# llc.net
KiCad netlist of a schematic drawn in EasyEDA Pro
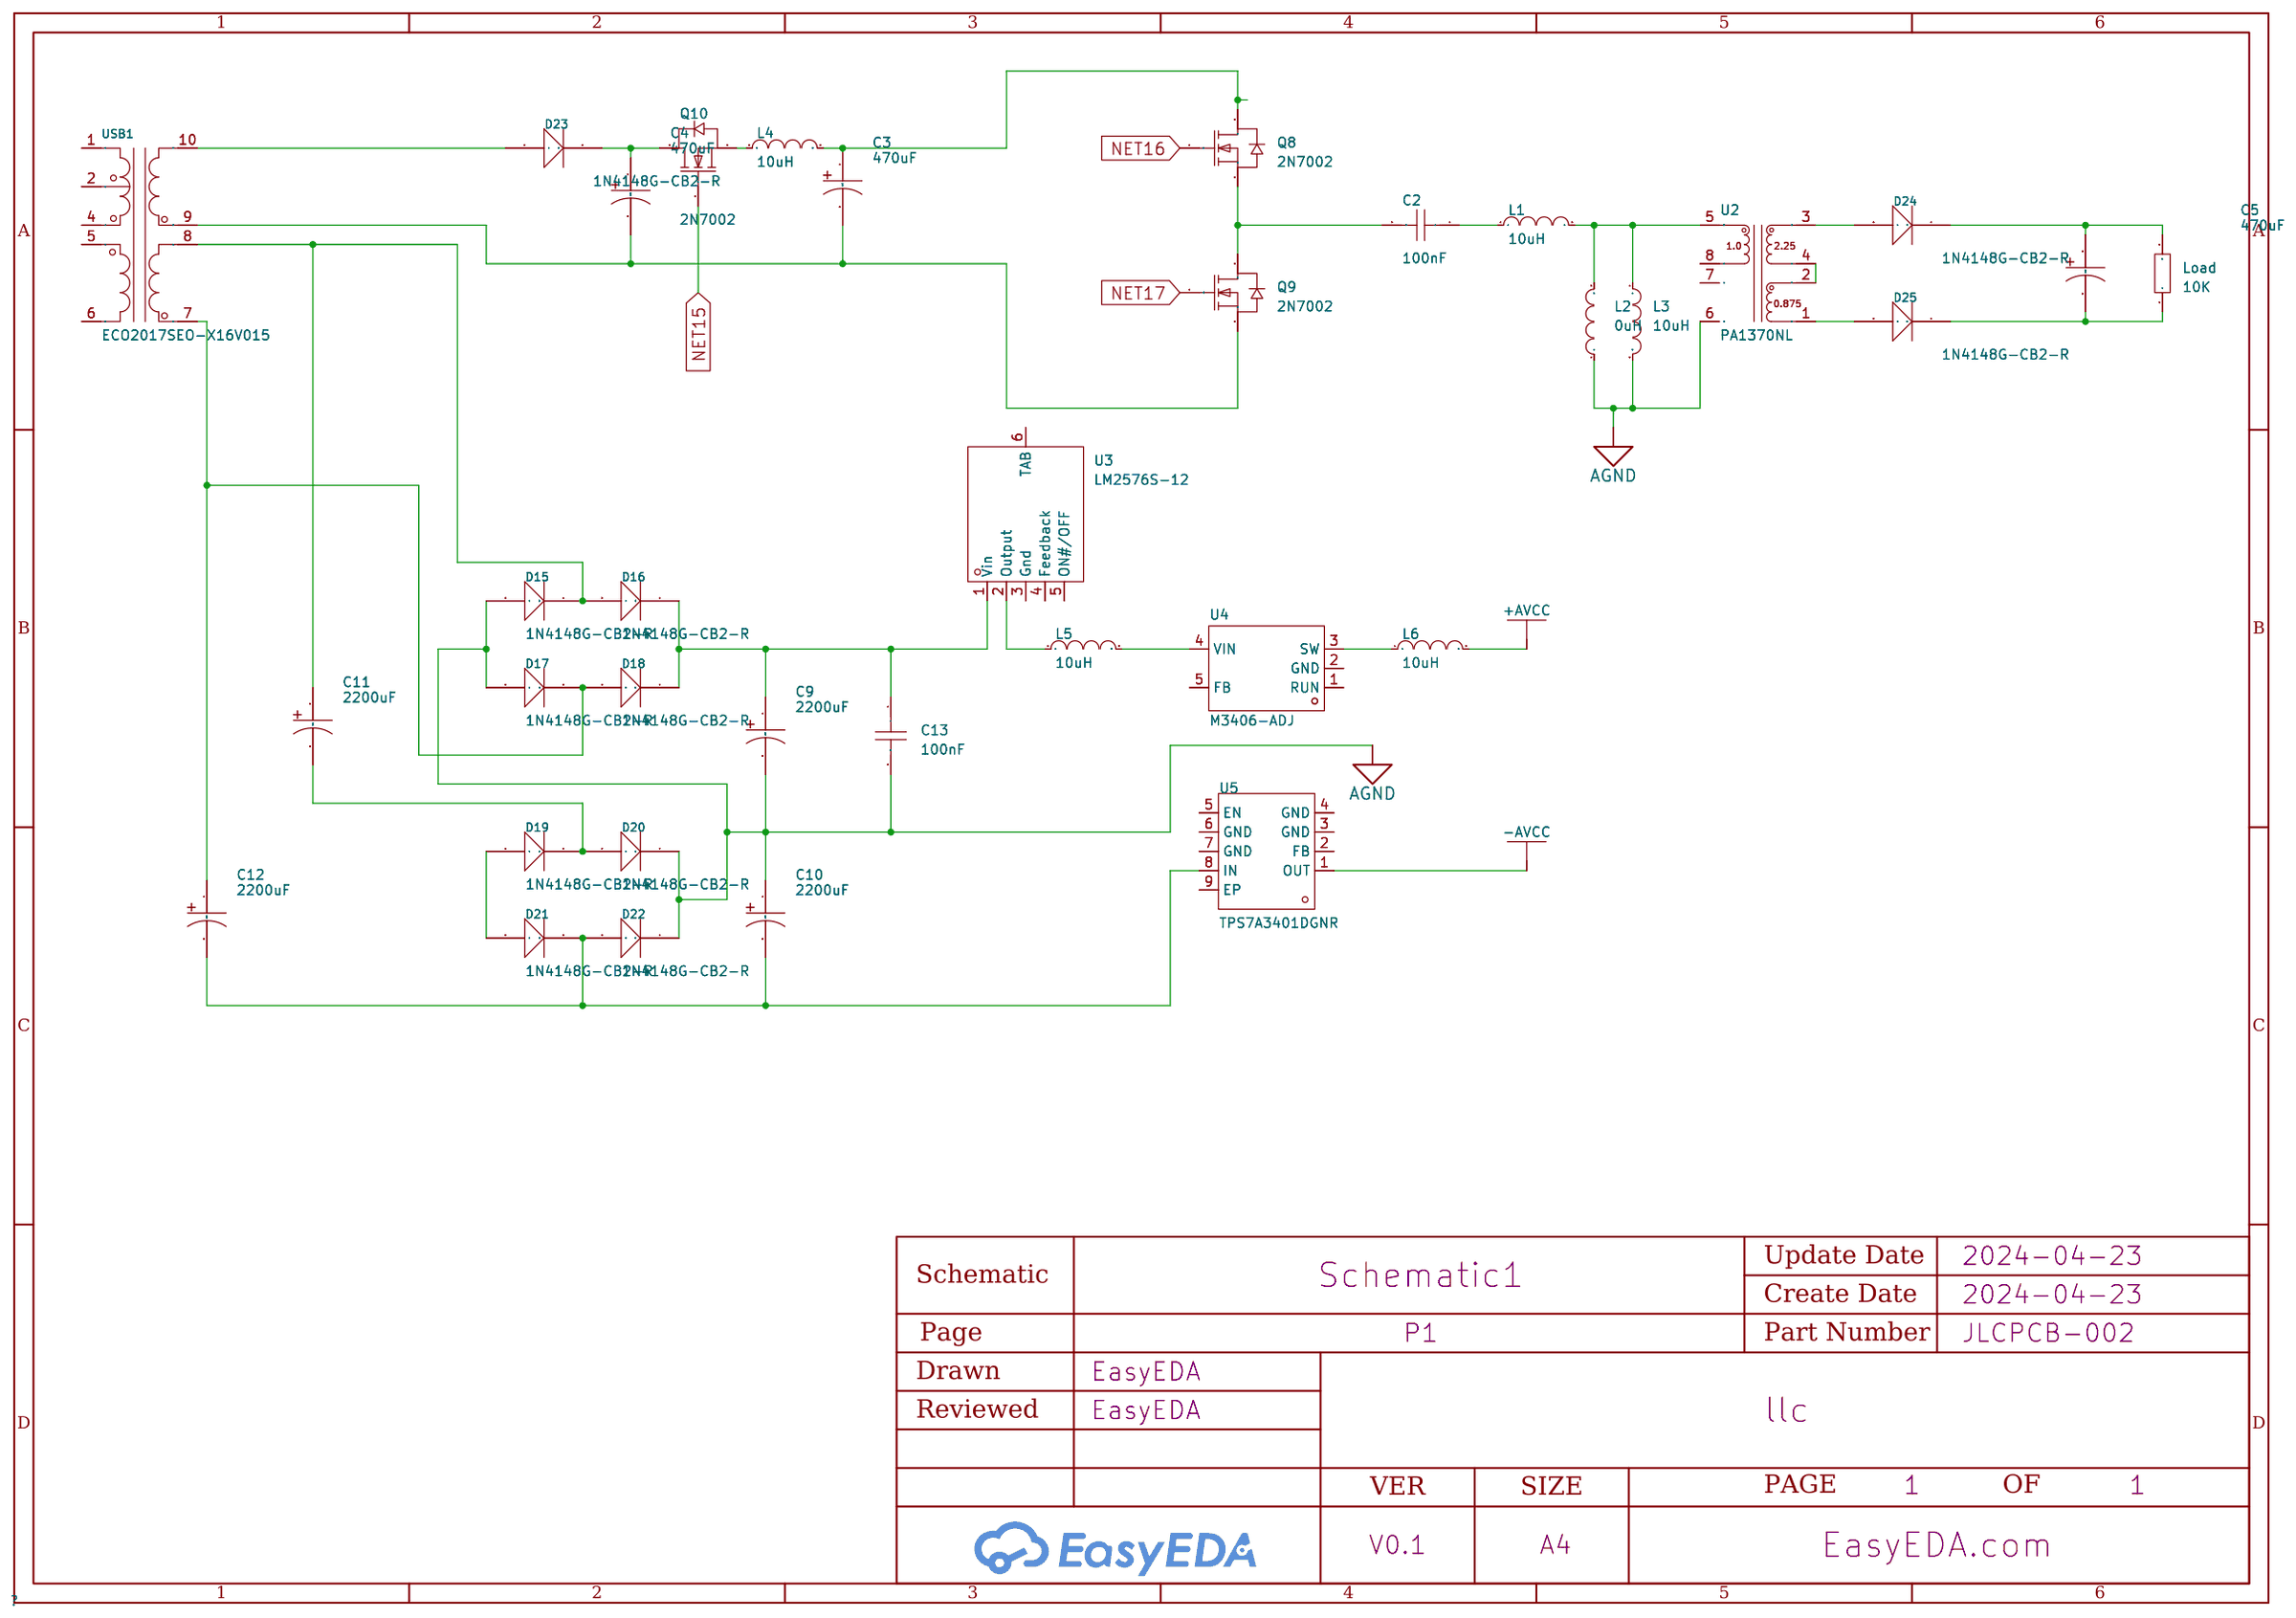
[diagram p0: P1]
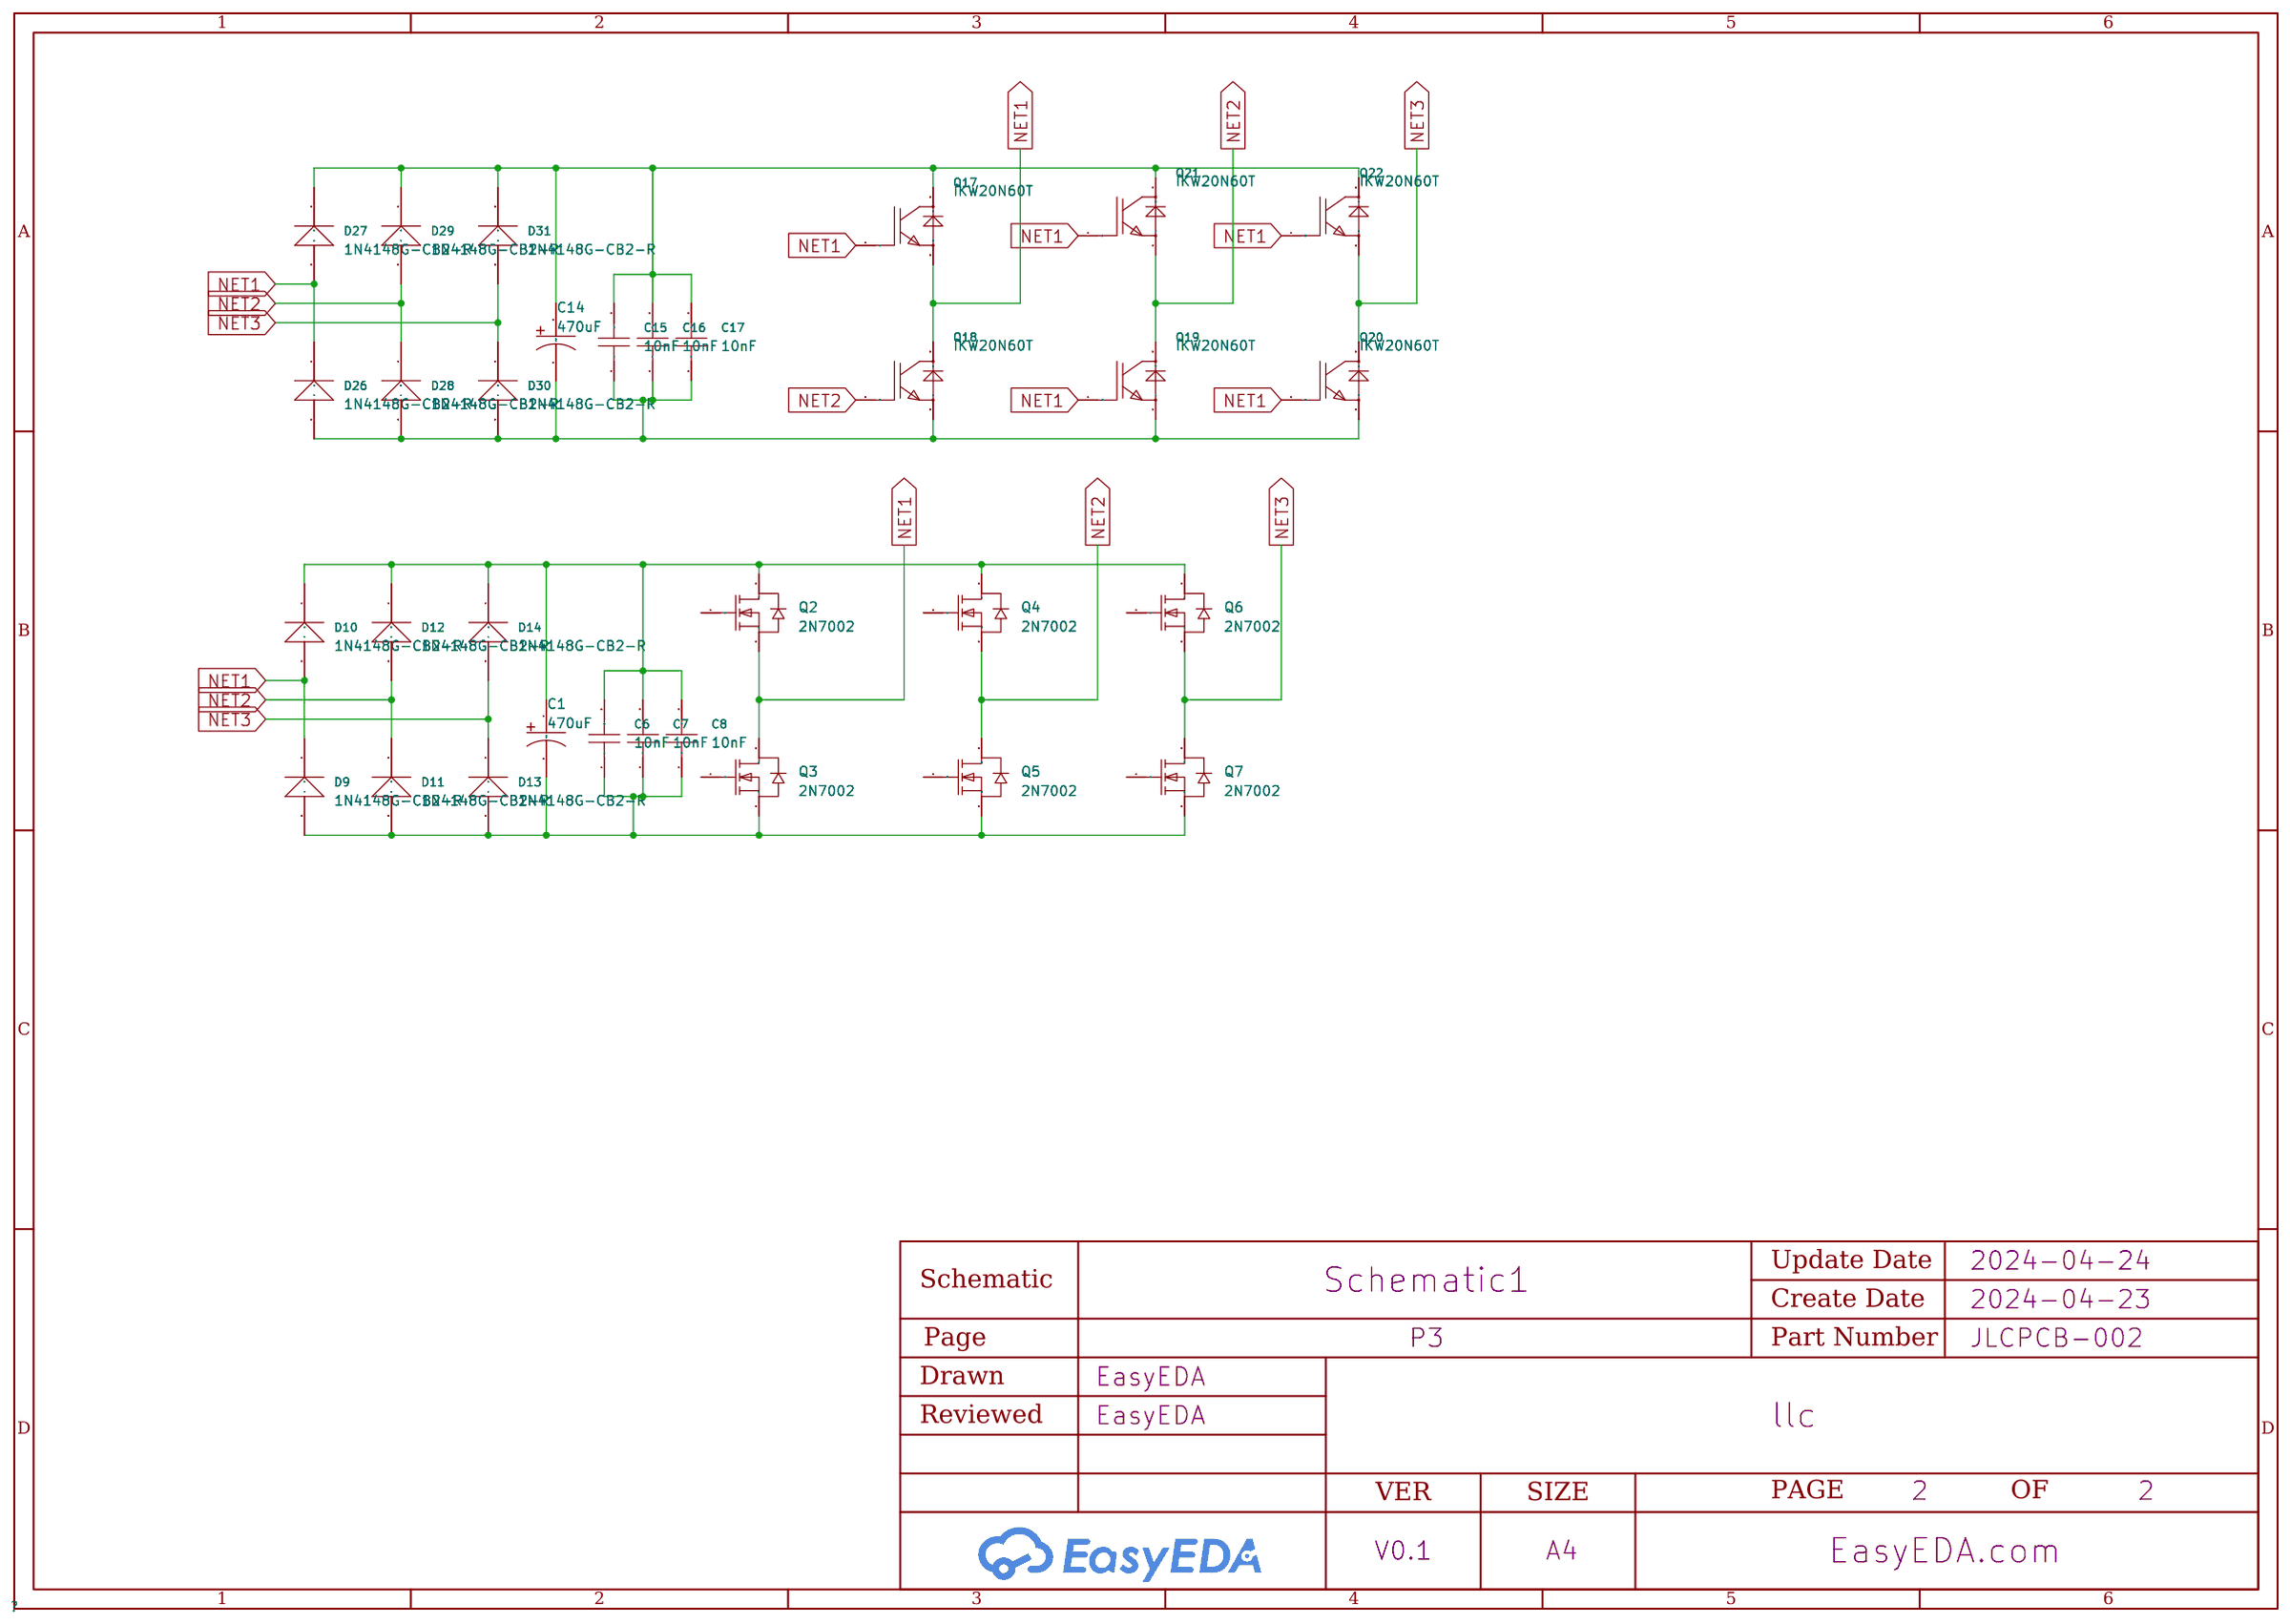
[diagram p1: P3]

(export (version "E")
  (design (tool "Eeschema 10.0.6"))
  (components
    (comp (ref "C2")
      (value "100nF")
      (footprint "easyedapro:C0603")
      (libsource (lib "easyedapro") (part "CAP"))
    )
    (comp (ref "C3")
      (value "470uF")
      (footprint "easyedapro:CAP-TH_BD35.0-P10.00-D2.3-FD")
      (fields (field (name "Manufacturer Part") "B43545S7477M001") (field (name "Manufacturer") "TDK"))
      (libsource (lib "easyedapro") (part "B43545S7477M001"))
    )
    (comp (ref "C4")
      (value "470uF")
      (footprint "easyedapro:CAP-TH_BD35.0-P10.00-D2.3-FD")
      (fields (field (name "Manufacturer Part") "B43545S7477M001") (field (name "Manufacturer") "TDK"))
      (libsource (lib "easyedapro") (part "B43545S7477M001"))
    )
    (comp (ref "C5")
      (value "470uF")
      (footprint "easyedapro:CAP-TH_BD35.0-P10.00-D2.3-FD")
      (fields (field (name "Manufacturer Part") "B43545S7477M001") (field (name "Manufacturer") "TDK"))
      (libsource (lib "easyedapro") (part "B43545S7477M001"))
    )
    (comp (ref "C9")
      (value "2200uF")
      (footprint "easyedapro:CAP-TH_BD12.5-P5.00-D0.6-FD")
      (fields (field (name "Manufacturer Part") "RGA222M1EBK-1325") (field (name "Manufacturer") "lelon(立隆)"))
      (libsource (lib "easyedapro") (part "RGA222M1EBK-1325"))
    )
    (comp (ref "C10")
      (value "2200uF")
      (footprint "easyedapro:CAP-TH_BD12.5-P5.00-D0.6-FD")
      (fields (field (name "Manufacturer Part") "RGA222M1EBK-1325") (field (name "Manufacturer") "lelon(立隆)"))
      (libsource (lib "easyedapro") (part "RGA222M1EBK-1325"))
    )
    (comp (ref "C11")
      (value "2200uF")
      (footprint "easyedapro:CAP-TH_BD12.5-P5.00-D0.6-FD")
      (fields (field (name "Manufacturer Part") "RGA222M1EBK-1325") (field (name "Manufacturer") "lelon(立隆)"))
      (libsource (lib "easyedapro") (part "RGA222M1EBK-1325"))
    )
    (comp (ref "C12")
      (value "2200uF")
      (footprint "easyedapro:CAP-TH_BD12.5-P5.00-D0.6-FD")
      (fields (field (name "Manufacturer Part") "RGA222M1EBK-1325") (field (name "Manufacturer") "lelon(立隆)"))
      (libsource (lib "easyedapro") (part "RGA222M1EBK-1325"))
    )
    (comp (ref "C13")
      (value "100nF")
      (footprint "easyedapro:C0603")
      (libsource (lib "easyedapro") (part "CAP"))
    )
    (comp (ref "D15")
      (value "1N4148G-CB2-R")
      (footprint "easyedapro:SOD-323_L1.8-W1.3-LS2.5-RD")
      (fields (field (name "Manufacturer") "UTC(友顺)"))
      (libsource (lib "easyedapro") (part "1N4148G-CB2-R"))
    )
    (comp (ref "D16")
      (value "1N4148G-CB2-R")
      (footprint "easyedapro:SOD-323_L1.8-W1.3-LS2.5-RD")
      (fields (field (name "Manufacturer") "UTC(友顺)"))
      (libsource (lib "easyedapro") (part "1N4148G-CB2-R"))
    )
    (comp (ref "D17")
      (value "1N4148G-CB2-R")
      (footprint "easyedapro:SOD-323_L1.8-W1.3-LS2.5-RD")
      (fields (field (name "Manufacturer") "UTC(友顺)"))
      (libsource (lib "easyedapro") (part "1N4148G-CB2-R"))
    )
    (comp (ref "D18")
      (value "1N4148G-CB2-R")
      (footprint "easyedapro:SOD-323_L1.8-W1.3-LS2.5-RD")
      (fields (field (name "Manufacturer") "UTC(友顺)"))
      (libsource (lib "easyedapro") (part "1N4148G-CB2-R"))
    )
    (comp (ref "D19")
      (value "1N4148G-CB2-R")
      (footprint "easyedapro:SOD-323_L1.8-W1.3-LS2.5-RD")
      (fields (field (name "Manufacturer") "UTC(友顺)"))
      (libsource (lib "easyedapro") (part "1N4148G-CB2-R"))
    )
    (comp (ref "D20")
      (value "1N4148G-CB2-R")
      (footprint "easyedapro:SOD-323_L1.8-W1.3-LS2.5-RD")
      (fields (field (name "Manufacturer") "UTC(友顺)"))
      (libsource (lib "easyedapro") (part "1N4148G-CB2-R"))
    )
    (comp (ref "D21")
      (value "1N4148G-CB2-R")
      (footprint "easyedapro:SOD-323_L1.8-W1.3-LS2.5-RD")
      (fields (field (name "Manufacturer") "UTC(友顺)"))
      (libsource (lib "easyedapro") (part "1N4148G-CB2-R"))
    )
    (comp (ref "D22")
      (value "1N4148G-CB2-R")
      (footprint "easyedapro:SOD-323_L1.8-W1.3-LS2.5-RD")
      (fields (field (name "Manufacturer") "UTC(友顺)"))
      (libsource (lib "easyedapro") (part "1N4148G-CB2-R"))
    )
    (comp (ref "D23")
      (value "1N4148G-CB2-R")
      (footprint "easyedapro:SOD-323_L1.8-W1.3-LS2.5-RD")
      (fields (field (name "Manufacturer") "UTC(友顺)"))
      (libsource (lib "easyedapro") (part "1N4148G-CB2-R"))
    )
    (comp (ref "D24")
      (value "1N4148G-CB2-R")
      (footprint "easyedapro:SOD-323_L1.8-W1.3-LS2.5-RD")
      (fields (field (name "Manufacturer") "UTC(友顺)"))
      (libsource (lib "easyedapro") (part "1N4148G-CB2-R"))
    )
    (comp (ref "D25")
      (value "1N4148G-CB2-R")
      (footprint "easyedapro:SOD-323_L1.8-W1.3-LS2.5-RD")
      (fields (field (name "Manufacturer") "UTC(友顺)"))
      (libsource (lib "easyedapro") (part "1N4148G-CB2-R"))
    )
    (comp (ref "L1") (value "10uH") (footprint "easyedapro:L0603") (libsource (lib "easyedapro") (part "电感")))
    (comp (ref "L2") (value "0uH") (footprint "easyedapro:L0603") (libsource (lib "easyedapro") (part "电感")))
    (comp (ref "L3") (value "10uH") (footprint "easyedapro:L0603") (libsource (lib "easyedapro") (part "电感")))
    (comp (ref "L4") (value "10uH") (footprint "easyedapro:L0603") (libsource (lib "easyedapro") (part "电感")))
    (comp (ref "L5") (value "10uH") (footprint "easyedapro:L0603") (libsource (lib "easyedapro") (part "电感")))
    (comp (ref "L6") (value "10uH") (footprint "easyedapro:L0603") (libsource (lib "easyedapro") (part "电感")))
    (comp (ref "Load")
      (value "10K")
      (footprint "easyedapro:R0603")
      (libsource (lib "easyedapro") (part "Res"))
    )
    (comp (ref "Q8")
      (value "2N7002")
      (footprint "easyedapro:SOT-23-3_L2.9-W1.3-P1.90-LS2.4-BR")
      (fields (field (name "Manufacturer") "CJ(江苏长电/长晶)"))
      (libsource (lib "easyedapro") (part "2N7002"))
    )
    (comp (ref "Q9")
      (value "2N7002")
      (footprint "easyedapro:SOT-23-3_L2.9-W1.3-P1.90-LS2.4-BR")
      (fields (field (name "Manufacturer") "CJ(江苏长电/长晶)"))
      (libsource (lib "easyedapro") (part "2N7002"))
    )
    (comp (ref "Q10")
      (value "2N7002")
      (footprint "easyedapro:SOT-23-3_L2.9-W1.3-P1.90-LS2.4-BR")
      (fields (field (name "Manufacturer") "CJ(江苏长电/长晶)"))
      (libsource (lib "easyedapro") (part "2N7002"))
    )
    (comp (ref "U2")
      (value "PA1370NL")
      (footprint "easyedapro:XFMR-SMD_PA1370NL")
      (description "Inductor:20.4uH operating temperature:-40°C~+130°C operating temperature:-40°C~+130°C")
      (fields (field (name "Manufacturer") "PULSE(普思)"))
      (libsource (lib "easyedapro") (part "PA1370NL"))
    )
    (comp (ref "U3")
      (value "LM2576S-12")
      (footprint "easyedapro:TO-263-5_L10.2-W8.9-P1.70-BR")
      (fields (field (name "Manufacturer") "UMW(友台半导体)"))
      (libsource (lib "easyedapro") (part "LM2576S-12_C347414"))
    )
    (comp (ref "U4")
      (value "M3406-ADJ")
      (footprint "easyedapro:SOT-23-5_L3.0-W1.7-P0.95-LS2.8-BR")
      (fields (field (name "Manufacturer") "西安航天民芯"))
      (libsource (lib "easyedapro") (part "M3406"))
    )
    (comp (ref "U5")
      (value "TPS7A3401DGNR")
      (footprint "easyedapro:MSOP-8_L3.0-W3.0-P0.65-LS4.9-BL-EP")
      (fields (field (name "Manufacturer") "TI(德州仪器)"))
      (libsource (lib "easyedapro") (part "TPS7A3401DGNR"))
    )
    (comp (ref "USB1")
      (value "ECO2017SEO-X16V015")
      (footprint "easyedapro:XFMR-TH_ECO2017SEO-X16V015")
      (fields (field (name "Manufacturer") "TDK"))
      (libsource (lib "easyedapro") (part "ECO2017SEO-X16V015"))
    )
    (comp (ref "C1")
      (value "470uF")
      (footprint "easyedapro:CAP-TH_BD35.0-P10.00-D2.3-FD")
      (fields (field (name "Manufacturer Part") "B43545S7477M001") (field (name "Manufacturer") "TDK"))
      (libsource (lib "easyedapro") (part "B43545S7477M001"))
    )
    (comp (ref "C6")
      (value "10nF")
      (footprint "easyedapro:CAP-TH_L14.0-W5.0-P7.50-D0.6-LS3.0")
      (fields
        (field (name "Manufacturer Part") "Y5V103M2KV16CC0204")
        (field (name "Manufacturer") "KNSCHA(科尼盛)")
      )
      (libsource (lib "easyedapro") (part "Y5V103M2KV16CC0204"))
    )
    (comp (ref "C7")
      (value "10nF")
      (footprint "easyedapro:CAP-TH_L14.0-W5.0-P7.50-D0.6-LS3.0")
      (fields
        (field (name "Manufacturer Part") "Y5V103M2KV16CC0204")
        (field (name "Manufacturer") "KNSCHA(科尼盛)")
      )
      (libsource (lib "easyedapro") (part "Y5V103M2KV16CC0204"))
    )
    (comp (ref "C8")
      (value "10nF")
      (footprint "easyedapro:CAP-TH_L14.0-W5.0-P7.50-D0.6-LS3.0")
      (fields
        (field (name "Manufacturer Part") "Y5V103M2KV16CC0204")
        (field (name "Manufacturer") "KNSCHA(科尼盛)")
      )
      (libsource (lib "easyedapro") (part "Y5V103M2KV16CC0204"))
    )
    (comp (ref "C14")
      (value "470uF")
      (footprint "easyedapro:CAP-TH_BD35.0-P10.00-D2.3-FD")
      (fields (field (name "Manufacturer Part") "B43545S7477M001") (field (name "Manufacturer") "TDK"))
      (libsource (lib "easyedapro") (part "B43545S7477M001"))
    )
    (comp (ref "C15")
      (value "10nF")
      (footprint "easyedapro:CAP-TH_L14.0-W5.0-P7.50-D0.6-LS3.0")
      (fields
        (field (name "Manufacturer Part") "Y5V103M2KV16CC0204")
        (field (name "Manufacturer") "KNSCHA(科尼盛)")
      )
      (libsource (lib "easyedapro") (part "Y5V103M2KV16CC0204"))
    )
    (comp (ref "C16")
      (value "10nF")
      (footprint "easyedapro:CAP-TH_L14.0-W5.0-P7.50-D0.6-LS3.0")
      (fields
        (field (name "Manufacturer Part") "Y5V103M2KV16CC0204")
        (field (name "Manufacturer") "KNSCHA(科尼盛)")
      )
      (libsource (lib "easyedapro") (part "Y5V103M2KV16CC0204"))
    )
    (comp (ref "C17")
      (value "10nF")
      (footprint "easyedapro:CAP-TH_L14.0-W5.0-P7.50-D0.6-LS3.0")
      (fields
        (field (name "Manufacturer Part") "Y5V103M2KV16CC0204")
        (field (name "Manufacturer") "KNSCHA(科尼盛)")
      )
      (libsource (lib "easyedapro") (part "Y5V103M2KV16CC0204"))
    )
    (comp (ref "D9")
      (value "1N4148G-CB2-R")
      (footprint "easyedapro:SOD-323_L1.8-W1.3-LS2.5-RD")
      (fields (field (name "Manufacturer") "UTC(友顺)"))
      (libsource (lib "easyedapro") (part "1N4148G-CB2-R"))
    )
    (comp (ref "D10")
      (value "1N4148G-CB2-R")
      (footprint "easyedapro:SOD-323_L1.8-W1.3-LS2.5-RD")
      (fields (field (name "Manufacturer") "UTC(友顺)"))
      (libsource (lib "easyedapro") (part "1N4148G-CB2-R"))
    )
    (comp (ref "D11")
      (value "1N4148G-CB2-R")
      (footprint "easyedapro:SOD-323_L1.8-W1.3-LS2.5-RD")
      (fields (field (name "Manufacturer") "UTC(友顺)"))
      (libsource (lib "easyedapro") (part "1N4148G-CB2-R"))
    )
    (comp (ref "D12")
      (value "1N4148G-CB2-R")
      (footprint "easyedapro:SOD-323_L1.8-W1.3-LS2.5-RD")
      (fields (field (name "Manufacturer") "UTC(友顺)"))
      (libsource (lib "easyedapro") (part "1N4148G-CB2-R"))
    )
    (comp (ref "D13")
      (value "1N4148G-CB2-R")
      (footprint "easyedapro:SOD-323_L1.8-W1.3-LS2.5-RD")
      (fields (field (name "Manufacturer") "UTC(友顺)"))
      (libsource (lib "easyedapro") (part "1N4148G-CB2-R"))
    )
    (comp (ref "D14")
      (value "1N4148G-CB2-R")
      (footprint "easyedapro:SOD-323_L1.8-W1.3-LS2.5-RD")
      (fields (field (name "Manufacturer") "UTC(友顺)"))
      (libsource (lib "easyedapro") (part "1N4148G-CB2-R"))
    )
    (comp (ref "D26")
      (value "1N4148G-CB2-R")
      (footprint "easyedapro:SOD-323_L1.8-W1.3-LS2.5-RD")
      (fields (field (name "Manufacturer") "UTC(友顺)"))
      (libsource (lib "easyedapro") (part "1N4148G-CB2-R"))
    )
    (comp (ref "D27")
      (value "1N4148G-CB2-R")
      (footprint "easyedapro:SOD-323_L1.8-W1.3-LS2.5-RD")
      (fields (field (name "Manufacturer") "UTC(友顺)"))
      (libsource (lib "easyedapro") (part "1N4148G-CB2-R"))
    )
    (comp (ref "D28")
      (value "1N4148G-CB2-R")
      (footprint "easyedapro:SOD-323_L1.8-W1.3-LS2.5-RD")
      (fields (field (name "Manufacturer") "UTC(友顺)"))
      (libsource (lib "easyedapro") (part "1N4148G-CB2-R"))
    )
    (comp (ref "D29")
      (value "1N4148G-CB2-R")
      (footprint "easyedapro:SOD-323_L1.8-W1.3-LS2.5-RD")
      (fields (field (name "Manufacturer") "UTC(友顺)"))
      (libsource (lib "easyedapro") (part "1N4148G-CB2-R"))
    )
    (comp (ref "D30")
      (value "1N4148G-CB2-R")
      (footprint "easyedapro:SOD-323_L1.8-W1.3-LS2.5-RD")
      (fields (field (name "Manufacturer") "UTC(友顺)"))
      (libsource (lib "easyedapro") (part "1N4148G-CB2-R"))
    )
    (comp (ref "D31")
      (value "1N4148G-CB2-R")
      (footprint "easyedapro:SOD-323_L1.8-W1.3-LS2.5-RD")
      (fields (field (name "Manufacturer") "UTC(友顺)"))
      (libsource (lib "easyedapro") (part "1N4148G-CB2-R"))
    )
    (comp (ref "Q2")
      (value "2N7002")
      (footprint "easyedapro:SOT-23-3_L2.9-W1.3-P1.90-LS2.4-BR")
      (fields (field (name "Manufacturer") "CJ(江苏长电/长晶)"))
      (libsource (lib "easyedapro") (part "2N7002"))
    )
    (comp (ref "Q3")
      (value "2N7002")
      (footprint "easyedapro:SOT-23-3_L2.9-W1.3-P1.90-LS2.4-BR")
      (fields (field (name "Manufacturer") "CJ(江苏长电/长晶)"))
      (libsource (lib "easyedapro") (part "2N7002"))
    )
    (comp (ref "Q4")
      (value "2N7002")
      (footprint "easyedapro:SOT-23-3_L2.9-W1.3-P1.90-LS2.4-BR")
      (fields (field (name "Manufacturer") "CJ(江苏长电/长晶)"))
      (libsource (lib "easyedapro") (part "2N7002"))
    )
    (comp (ref "Q5")
      (value "2N7002")
      (footprint "easyedapro:SOT-23-3_L2.9-W1.3-P1.90-LS2.4-BR")
      (fields (field (name "Manufacturer") "CJ(江苏长电/长晶)"))
      (libsource (lib "easyedapro") (part "2N7002"))
    )
    (comp (ref "Q6")
      (value "2N7002")
      (footprint "easyedapro:SOT-23-3_L2.9-W1.3-P1.90-LS2.4-BR")
      (fields (field (name "Manufacturer") "CJ(江苏长电/长晶)"))
      (libsource (lib "easyedapro") (part "2N7002"))
    )
    (comp (ref "Q7")
      (value "2N7002")
      (footprint "easyedapro:SOT-23-3_L2.9-W1.3-P1.90-LS2.4-BR")
      (fields (field (name "Manufacturer") "CJ(江苏长电/长晶)"))
      (libsource (lib "easyedapro") (part "2N7002"))
    )
    (comp (ref "Q17")
      (value "IKW20N60T")
      (footprint "easyedapro:TO-247AC-3_L15.8-W5.0-P5.46-L")
      (fields (field (name "Manufacturer") "Infineon(英飞凌)"))
      (libsource (lib "easyedapro") (part "IKW20N60T"))
    )
    (comp (ref "Q18")
      (value "IKW20N60T")
      (footprint "easyedapro:TO-247AC-3_L15.8-W5.0-P5.46-L")
      (fields (field (name "Manufacturer") "Infineon(英飞凌)"))
      (libsource (lib "easyedapro") (part "IKW20N60T"))
    )
    (comp (ref "Q19")
      (value "IKW20N60T")
      (footprint "easyedapro:TO-247AC-3_L15.8-W5.0-P5.46-L")
      (fields (field (name "Manufacturer") "Infineon(英飞凌)"))
      (libsource (lib "easyedapro") (part "IKW20N60T"))
    )
    (comp (ref "Q20")
      (value "IKW20N60T")
      (footprint "easyedapro:TO-247AC-3_L15.8-W5.0-P5.46-L")
      (fields (field (name "Manufacturer") "Infineon(英飞凌)"))
      (libsource (lib "easyedapro") (part "IKW20N60T"))
    )
    (comp (ref "Q21")
      (value "IKW20N60T")
      (footprint "easyedapro:TO-247AC-3_L15.8-W5.0-P5.46-L")
      (fields (field (name "Manufacturer") "Infineon(英飞凌)"))
      (libsource (lib "easyedapro") (part "IKW20N60T"))
    )
    (comp (ref "Q22")
      (value "IKW20N60T")
      (footprint "easyedapro:TO-247AC-3_L15.8-W5.0-P5.46-L")
      (fields (field (name "Manufacturer") "Infineon(英飞凌)"))
      (libsource (lib "easyedapro") (part "IKW20N60T"))
    )
  )
  (nets
    (net (code "1") (name "+AVCC") (class "Default")
      (node (ref "L6") (pin "2") (pinfunction "2_2") (pintype "input"))
    )
    (net (code "2") (name "-AVCC") (class "Default")
      (node (ref "U5") (pin "1") (pinfunction "OUT_1") (pintype "unspecified"))
    )
    (net (code "3") (name "AGND") (class "Default")
      (node (ref "C10") (pin "1") (pinfunction "1_1") (pintype "input"))
      (node (ref "C13") (pin "2") (pinfunction "2_2") (pintype "input"))
      (node (ref "C9") (pin "2") (pinfunction "2_2") (pintype "input"))
      (node (ref "D15") (pin "2") (pinfunction "A_2") (pintype "input"))
      (node (ref "D17") (pin "2") (pinfunction "A_2") (pintype "input"))
      (node (ref "D20") (pin "1") (pinfunction "C_1") (pintype "input"))
      (node (ref "D22") (pin "1") (pinfunction "C_1") (pintype "input"))
      (node (ref "L2") (pin "1") (pinfunction "1_1") (pintype "input"))
      (node (ref "L3") (pin "2") (pinfunction "2_2") (pintype "input"))
      (node (ref "U2") (pin "6") (pinfunction "6_6") (pintype "unspecified"))
    )
    (net (code "4") (name "NET1") (class "Default")
      (node (ref "D10") (pin "2") (pinfunction "A_2") (pintype "input"))
      (node (ref "D26") (pin "1") (pinfunction "C_1") (pintype "input"))
      (node (ref "D27") (pin "2") (pinfunction "A_2") (pintype "input"))
      (node (ref "D9") (pin "1") (pinfunction "C_1") (pintype "input"))
      (node (ref "Q17") (pin "1") (pinfunction "G_1") (pintype "input"))
      (node (ref "Q17") (pin "3") (pinfunction "E_3") (pintype "input"))
      (node (ref "Q18") (pin "2") (pinfunction "C_2") (pintype "input"))
      (node (ref "Q19") (pin "1") (pinfunction "G_1") (pintype "input"))
      (node (ref "Q2") (pin "2") (pinfunction "S_2") (pintype "unspecified"))
      (node (ref "Q20") (pin "1") (pinfunction "G_1") (pintype "input"))
      (node (ref "Q21") (pin "1") (pinfunction "G_1") (pintype "input"))
      (node (ref "Q22") (pin "1") (pinfunction "G_1") (pintype "input"))
      (node (ref "Q3") (pin "3") (pinfunction "D_3") (pintype "unspecified"))
    )
    (net (code "5") (name "NET2") (class "Default")
      (node (ref "D11") (pin "1") (pinfunction "C_1") (pintype "input"))
      (node (ref "D12") (pin "2") (pinfunction "A_2") (pintype "input"))
      (node (ref "D28") (pin "1") (pinfunction "C_1") (pintype "input"))
      (node (ref "D29") (pin "2") (pinfunction "A_2") (pintype "input"))
      (node (ref "Q18") (pin "1") (pinfunction "G_1") (pintype "input"))
      (node (ref "Q19") (pin "2") (pinfunction "C_2") (pintype "input"))
      (node (ref "Q21") (pin "3") (pinfunction "E_3") (pintype "input"))
      (node (ref "Q4") (pin "2") (pinfunction "S_2") (pintype "unspecified"))
      (node (ref "Q5") (pin "3") (pinfunction "D_3") (pintype "unspecified"))
    )
    (net (code "6") (name "NET3") (class "Default")
      (node (ref "D13") (pin "1") (pinfunction "C_1") (pintype "input"))
      (node (ref "D14") (pin "2") (pinfunction "A_2") (pintype "input"))
      (node (ref "D30") (pin "1") (pinfunction "C_1") (pintype "input"))
      (node (ref "D31") (pin "2") (pinfunction "A_2") (pintype "input"))
      (node (ref "Q20") (pin "2") (pinfunction "C_2") (pintype "input"))
      (node (ref "Q22") (pin "3") (pinfunction "E_3") (pintype "input"))
      (node (ref "Q6") (pin "2") (pinfunction "S_2") (pintype "unspecified"))
      (node (ref "Q7") (pin "3") (pinfunction "D_3") (pintype "unspecified"))
    )
    (net (code "7") (name "NET15") (class "Default")
      (node (ref "Q10") (pin "1") (pinfunction "G_1") (pintype "unspecified"))
    )
    (net (code "8") (name "NET16") (class "Default")
      (node (ref "Q8") (pin "1") (pinfunction "G_1") (pintype "unspecified"))
    )
    (net (code "9") (name "NET17") (class "Default")
      (node (ref "Q9") (pin "1") (pinfunction "G_1") (pintype "unspecified"))
    )
    (net (code "10") (name "Net-(C2-Pad1)") (class "Default")
      (node (ref "C2") (pin "1") (pinfunction "1_1") (pintype "input"))
      (node (ref "L1") (pin "1") (pinfunction "1_1") (pintype "input"))
    )
    (net (code "11") (name "Net-(D10-C)") (class "Default")
      (node (ref "C1") (pin "1") (pinfunction "1_1") (pintype "input"))
      (node (ref "C6") (pin "2") (pinfunction "2_2") (pintype "input"))
      (node (ref "C7") (pin "2") (pinfunction "2_2") (pintype "input"))
      (node (ref "C8") (pin "2") (pinfunction "2_2") (pintype "input"))
      (node (ref "D10") (pin "1") (pinfunction "C_1") (pintype "input"))
      (node (ref "D12") (pin "1") (pinfunction "C_1") (pintype "input"))
      (node (ref "D14") (pin "1") (pinfunction "C_1") (pintype "input"))
      (node (ref "Q2") (pin "3") (pinfunction "D_3") (pintype "unspecified"))
      (node (ref "Q4") (pin "3") (pinfunction "D_3") (pintype "unspecified"))
      (node (ref "Q6") (pin "3") (pinfunction "D_3") (pintype "unspecified"))
    )
    (net (code "12") (name "Net-(D11-A)") (class "Default")
      (node (ref "C1") (pin "2") (pinfunction "2_2") (pintype "input"))
      (node (ref "C6") (pin "1") (pinfunction "1_1") (pintype "input"))
      (node (ref "C7") (pin "1") (pinfunction "1_1") (pintype "input"))
      (node (ref "C8") (pin "1") (pinfunction "1_1") (pintype "input"))
      (node (ref "D11") (pin "2") (pinfunction "A_2") (pintype "input"))
      (node (ref "D13") (pin "2") (pinfunction "A_2") (pintype "input"))
      (node (ref "D9") (pin "2") (pinfunction "A_2") (pintype "input"))
      (node (ref "Q3") (pin "2") (pinfunction "S_2") (pintype "unspecified"))
      (node (ref "Q5") (pin "2") (pinfunction "S_2") (pintype "unspecified"))
      (node (ref "Q7") (pin "2") (pinfunction "S_2") (pintype "unspecified"))
    )
    (net (code "13") (name "Net-(D15-C)") (class "Default")
      (node (ref "C11") (pin "1") (pinfunction "1_1") (pintype "input"))
      (node (ref "D15") (pin "1") (pinfunction "C_1") (pintype "input"))
      (node (ref "D16") (pin "2") (pinfunction "A_2") (pintype "input"))
      (node (ref "USB1") (pin "8") (pinfunction "8_8") (pintype "input"))
    )
    (net (code "14") (name "Net-(D16-C)") (class "Default")
      (node (ref "C13") (pin "1") (pinfunction "1_1") (pintype "input"))
      (node (ref "C9") (pin "1") (pinfunction "1_1") (pintype "input"))
      (node (ref "D16") (pin "1") (pinfunction "C_1") (pintype "input"))
      (node (ref "D18") (pin "1") (pinfunction "C_1") (pintype "input"))
      (node (ref "U3") (pin "1") (pinfunction "Vin_1") (pintype "unspecified"))
    )
    (net (code "15") (name "Net-(D17-C)") (class "Default")
      (node (ref "C12") (pin "1") (pinfunction "1_1") (pintype "input"))
      (node (ref "D17") (pin "1") (pinfunction "C_1") (pintype "input"))
      (node (ref "D18") (pin "2") (pinfunction "A_2") (pintype "input"))
      (node (ref "USB1") (pin "7") (pinfunction "7_7") (pintype "input"))
    )
    (net (code "16") (name "Net-(D19-A)") (class "Default")
      (node (ref "D19") (pin "2") (pinfunction "A_2") (pintype "input"))
      (node (ref "D21") (pin "2") (pinfunction "A_2") (pintype "input"))
    )
    (net (code "17") (name "Net-(D19-C)") (class "Default")
      (node (ref "C11") (pin "2") (pinfunction "2_2") (pintype "input"))
      (node (ref "D19") (pin "1") (pinfunction "C_1") (pintype "input"))
      (node (ref "D20") (pin "2") (pinfunction "A_2") (pintype "input"))
    )
    (net (code "18") (name "Net-(D21-C)") (class "Default")
      (node (ref "C10") (pin "2") (pinfunction "2_2") (pintype "input"))
      (node (ref "C12") (pin "2") (pinfunction "2_2") (pintype "input"))
      (node (ref "D21") (pin "1") (pinfunction "C_1") (pintype "input"))
      (node (ref "D22") (pin "2") (pinfunction "A_2") (pintype "input"))
      (node (ref "U5") (pin "8") (pinfunction "IN_8") (pintype "unspecified"))
    )
    (net (code "19") (name "Net-(D23-A)") (class "Default")
      (node (ref "D23") (pin "2") (pinfunction "A_2") (pintype "input"))
      (node (ref "USB1") (pin "10") (pinfunction "10_10") (pintype "input"))
    )
    (net (code "20") (name "Net-(D23-C)") (class "Default")
      (node (ref "C4") (pin "1") (pinfunction "1_1") (pintype "input"))
      (node (ref "D23") (pin "1") (pinfunction "C_1") (pintype "input"))
      (node (ref "Q10") (pin "3") (pinfunction "D_3") (pintype "unspecified"))
    )
    (net (code "21") (name "Net-(D24-A)") (class "Default")
      (node (ref "D24") (pin "2") (pinfunction "A_2") (pintype "input"))
      (node (ref "U2") (pin "3") (pinfunction "3_3") (pintype "unspecified"))
    )
    (net (code "22") (name "Net-(D24-C)") (class "Default")
      (node (ref "C5") (pin "1") (pinfunction "1_1") (pintype "input"))
      (node (ref "D24") (pin "1") (pinfunction "C_1") (pintype "input"))
      (node (ref "Load") (pin "2") (pinfunction "2_2") (pintype "input"))
    )
    (net (code "23") (name "Net-(D25-A)") (class "Default")
      (node (ref "D25") (pin "2") (pinfunction "A_2") (pintype "input"))
      (node (ref "U2") (pin "1") (pinfunction "1_1") (pintype "unspecified"))
    )
    (net (code "24") (name "Net-(D25-C)") (class "Default")
      (node (ref "C5") (pin "2") (pinfunction "2_2") (pintype "input"))
      (node (ref "D25") (pin "1") (pinfunction "C_1") (pintype "input"))
      (node (ref "Load") (pin "1") (pinfunction "1_1") (pintype "input"))
    )
    (net (code "25") (name "Net-(D26-A)") (class "Default")
      (node (ref "C14") (pin "2") (pinfunction "2_2") (pintype "input"))
      (node (ref "C15") (pin "1") (pinfunction "1_1") (pintype "input"))
      (node (ref "C16") (pin "1") (pinfunction "1_1") (pintype "input"))
      (node (ref "C17") (pin "1") (pinfunction "1_1") (pintype "input"))
      (node (ref "D26") (pin "2") (pinfunction "A_2") (pintype "input"))
      (node (ref "D28") (pin "2") (pinfunction "A_2") (pintype "input"))
      (node (ref "D30") (pin "2") (pinfunction "A_2") (pintype "input"))
      (node (ref "Q18") (pin "3") (pinfunction "E_3") (pintype "input"))
      (node (ref "Q19") (pin "3") (pinfunction "E_3") (pintype "input"))
      (node (ref "Q20") (pin "3") (pinfunction "E_3") (pintype "input"))
    )
    (net (code "26") (name "Net-(D27-C)") (class "Default")
      (node (ref "C14") (pin "1") (pinfunction "1_1") (pintype "input"))
      (node (ref "C15") (pin "2") (pinfunction "2_2") (pintype "input"))
      (node (ref "C16") (pin "2") (pinfunction "2_2") (pintype "input"))
      (node (ref "C17") (pin "2") (pinfunction "2_2") (pintype "input"))
      (node (ref "D27") (pin "1") (pinfunction "C_1") (pintype "input"))
      (node (ref "D29") (pin "1") (pinfunction "C_1") (pintype "input"))
      (node (ref "D31") (pin "1") (pinfunction "C_1") (pintype "input"))
      (node (ref "Q17") (pin "2") (pinfunction "C_2") (pintype "input"))
      (node (ref "Q21") (pin "2") (pinfunction "C_2") (pintype "input"))
      (node (ref "Q22") (pin "2") (pinfunction "C_2") (pintype "input"))
    )
    (net (code "27") (name "Net-(L1-Pad2)") (class "Default")
      (node (ref "L1") (pin "2") (pinfunction "2_2") (pintype "input"))
      (node (ref "L2") (pin "2") (pinfunction "2_2") (pintype "input"))
      (node (ref "L3") (pin "1") (pinfunction "1_1") (pintype "input"))
      (node (ref "U2") (pin "5") (pinfunction "5_5") (pintype "unspecified"))
    )
    (net (code "28") (name "Net-(Q8-D)") (class "Default")
      (node (ref "C3") (pin "1") (pinfunction "1_1") (pintype "input"))
      (node (ref "L4") (pin "2") (pinfunction "2_2") (pintype "input"))
      (node (ref "Q8") (pin "3") (pinfunction "D_3") (pintype "unspecified"))
    )
    (net (code "29") (name "Net-(Q8-S)") (class "Default")
      (node (ref "C2") (pin "2") (pinfunction "2_2") (pintype "input"))
      (node (ref "Q8") (pin "2") (pinfunction "S_2") (pintype "unspecified"))
      (node (ref "Q9") (pin "3") (pinfunction "D_3") (pintype "unspecified"))
    )
    (net (code "30") (name "Net-(Q9-S)") (class "Default")
      (node (ref "C3") (pin "2") (pinfunction "2_2") (pintype "input"))
      (node (ref "C4") (pin "2") (pinfunction "2_2") (pintype "input"))
      (node (ref "Q9") (pin "2") (pinfunction "S_2") (pintype "unspecified"))
      (node (ref "USB1") (pin "9") (pinfunction "9_9") (pintype "input"))
    )
    (net (code "31") (name "Net-(Q10-S)") (class "Default")
      (node (ref "L4") (pin "1") (pinfunction "1_1") (pintype "input"))
      (node (ref "Q10") (pin "2") (pinfunction "S_2") (pintype "unspecified"))
    )
    (net (code "32") (name "Net-(U2-Pad2)") (class "Default")
      (node (ref "U2") (pin "2") (pinfunction "2_2") (pintype "unspecified"))
      (node (ref "U2") (pin "4") (pinfunction "4_4") (pintype "unspecified"))
    )
    (net (code "33") (name "Net-(U3-Output)") (class "Default")
      (node (ref "L5") (pin "1") (pinfunction "1_1") (pintype "input"))
      (node (ref "U3") (pin "2") (pinfunction "Output_2") (pintype "unspecified"))
    )
    (net (code "34") (name "Net-(U4-SW)") (class "Default")
      (node (ref "L6") (pin "1") (pinfunction "1_1") (pintype "input"))
      (node (ref "U4") (pin "3") (pinfunction "SW_3") (pintype "input"))
    )
    (net (code "35") (name "Net-(U4-VIN)") (class "Default")
      (node (ref "L5") (pin "2") (pinfunction "2_2") (pintype "input"))
      (node (ref "U4") (pin "4") (pinfunction "VIN_4") (pintype "input"))
    )
    (net (code "36") (name "unconnected-(Q2-G-Pad1)") (class "Default")
      (node (ref "Q2") (pin "1") (pinfunction "G_1") (pintype "unspecified"))
    )
    (net (code "37") (name "unconnected-(Q3-G-Pad1)") (class "Default")
      (node (ref "Q3") (pin "1") (pinfunction "G_1") (pintype "unspecified"))
    )
    (net (code "38") (name "unconnected-(Q4-G-Pad1)") (class "Default")
      (node (ref "Q4") (pin "1") (pinfunction "G_1") (pintype "unspecified"))
    )
    (net (code "39") (name "unconnected-(Q5-G-Pad1)") (class "Default")
      (node (ref "Q5") (pin "1") (pinfunction "G_1") (pintype "unspecified"))
    )
    (net (code "40") (name "unconnected-(Q6-G-Pad1)") (class "Default")
      (node (ref "Q6") (pin "1") (pinfunction "G_1") (pintype "unspecified"))
    )
    (net (code "41") (name "unconnected-(Q7-G-Pad1)") (class "Default")
      (node (ref "Q7") (pin "1") (pinfunction "G_1") (pintype "unspecified"))
    )
    (net (code "42") (name "unconnected-(U2-Pad7)") (class "Default")
      (node (ref "U2") (pin "7") (pinfunction "7_7") (pintype "unspecified"))
    )
    (net (code "43") (name "unconnected-(U2-Pad8)") (class "Default")
      (node (ref "U2") (pin "8") (pinfunction "8_8") (pintype "unspecified"))
    )
    (net (code "44") (name "unconnected-(U3-Feedback-Pad4)") (class "Default")
      (node (ref "U3") (pin "4") (pinfunction "Feedback_4") (pintype "unspecified"))
    )
    (net (code "45") (name "unconnected-(U3-Gnd-Pad3)") (class "Default")
      (node (ref "U3") (pin "3") (pinfunction "Gnd_3") (pintype "unspecified"))
    )
    (net (code "46") (name "unconnected-(U3-ON#{slash}OFF-Pad5)") (class "Default")
      (node (ref "U3") (pin "5") (pinfunction "ON#/OFF_5") (pintype "unspecified"))
    )
    (net (code "47") (name "unconnected-(U3-TAB-Pad6)") (class "Default")
      (node (ref "U3") (pin "6") (pinfunction "TAB_6") (pintype "unspecified"))
    )
    (net (code "48") (name "unconnected-(U4-FB-Pad5)") (class "Default")
      (node (ref "U4") (pin "5") (pinfunction "FB_5") (pintype "input"))
    )
    (net (code "49") (name "unconnected-(U4-GND-Pad2)") (class "Default")
      (node (ref "U4") (pin "2") (pinfunction "GND_2") (pintype "input"))
    )
    (net (code "50") (name "unconnected-(U4-RUN-Pad1)") (class "Default")
      (node (ref "U4") (pin "1") (pinfunction "RUN_1") (pintype "input"))
    )
    (net (code "51") (name "unconnected-(U5-EN-Pad5)") (class "Default")
      (node (ref "U5") (pin "5") (pinfunction "EN_5") (pintype "unspecified"))
    )
    (net (code "52") (name "unconnected-(U5-EP-Pad9)") (class "Default")
      (node (ref "U5") (pin "9") (pinfunction "EP_9") (pintype "unspecified"))
    )
    (net (code "53") (name "unconnected-(U5-FB-Pad2)") (class "Default")
      (node (ref "U5") (pin "2") (pinfunction "FB_2") (pintype "unspecified"))
    )
    (net (code "54") (name "unconnected-(U5-GND-Pad3)") (class "Default")
      (node (ref "U5") (pin "3") (pinfunction "GND_3") (pintype "unspecified"))
    )
    (net (code "55") (name "unconnected-(U5-GND-Pad4)") (class "Default")
      (node (ref "U5") (pin "4") (pinfunction "GND_4") (pintype "unspecified"))
    )
    (net (code "56") (name "unconnected-(U5-GND-Pad6)") (class "Default")
      (node (ref "U5") (pin "6") (pinfunction "GND_6") (pintype "unspecified"))
    )
    (net (code "57") (name "unconnected-(U5-GND-Pad7)") (class "Default")
      (node (ref "U5") (pin "7") (pinfunction "GND_7") (pintype "unspecified"))
    )
    (net (code "58") (name "unconnected-(USB1-Pad1)") (class "Default")
      (node (ref "USB1") (pin "1") (pinfunction "1_1") (pintype "input"))
    )
    (net (code "59") (name "unconnected-(USB1-Pad2)") (class "Default")
      (node (ref "USB1") (pin "2") (pinfunction "2_2") (pintype "input"))
    )
    (net (code "60") (name "unconnected-(USB1-Pad4)") (class "Default")
      (node (ref "USB1") (pin "4") (pinfunction "4_4") (pintype "input"))
    )
    (net (code "61") (name "unconnected-(USB1-Pad5)") (class "Default")
      (node (ref "USB1") (pin "5") (pinfunction "5_5") (pintype "input"))
    )
    (net (code "62") (name "unconnected-(USB1-Pad6)") (class "Default")
      (node (ref "USB1") (pin "6") (pinfunction "6_6") (pintype "input"))
    )
  )
)
